# Flash.net
KiCad netlist of a schematic drawn in Altium Designer
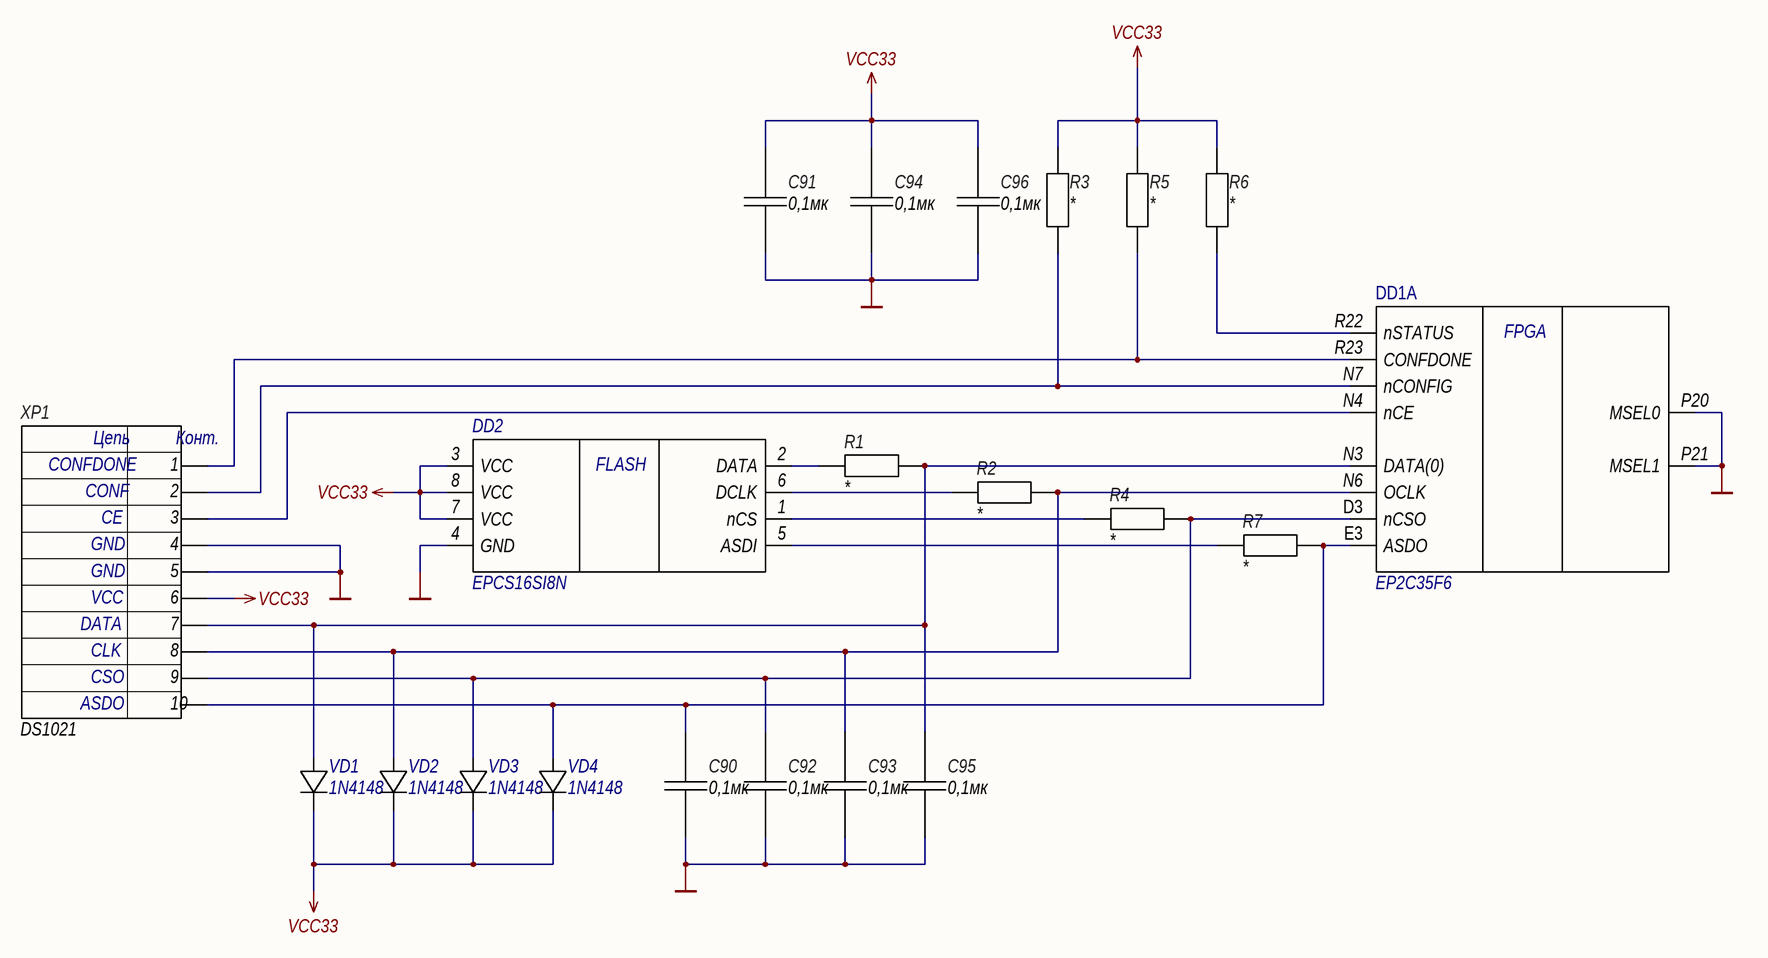
[diagram p0: Flash.SchDoc]

(export (version "E")
  (design (tool "Eeschema 10.0.6"))
  (components
    (comp (ref "C90")
      (value "0,1мк")
      (footprint "0603")
      (libsource (lib "FPGA_Automotibe_Radar_Lib") (part "Capacitor_0603"))
    )
    (comp (ref "C91")
      (value "0,1мк")
      (footprint "RESC1005X35N")
      (libsource (lib "FPGA_Automotibe_Radar_Lib") (part "Capacitor_0.1u"))
    )
    (comp (ref "C92")
      (value "0,1мк")
      (footprint "0603")
      (libsource (lib "FPGA_Automotibe_Radar_Lib") (part "Capacitor_0603"))
    )
    (comp (ref "C93")
      (value "0,1мк")
      (footprint "0603")
      (libsource (lib "FPGA_Automotibe_Radar_Lib") (part "Capacitor_0603"))
    )
    (comp (ref "C94")
      (value "0,1мк")
      (footprint "RESC1005X35N")
      (libsource (lib "FPGA_Automotibe_Radar_Lib") (part "Capacitor_0.1u"))
    )
    (comp (ref "C95")
      (value "0,1мк")
      (footprint "0603")
      (libsource (lib "FPGA_Automotibe_Radar_Lib") (part "Capacitor_0603"))
    )
    (comp (ref "C96")
      (value "0,1мк")
      (footprint "RESC1005X35N")
      (libsource (lib "FPGA_Automotibe_Radar_Lib") (part "Capacitor_0.1u"))
    )
    (comp (ref "DD1")
      (value "EP2C35F6")
      (footprint "BGA672CP100_26X26_2700X2700X240B60N")
      (libsource (lib "FPGA_Automotibe_Radar_Lib") (part "PLIS"))
    )
    (comp (ref "DD2")
      (value "EPCS16SI8N")
      (footprint "SOIC127P600X175-8N")
      (libsource (lib "FPGA_Automotibe_Radar_Lib") (part "FLASH"))
    )
    (comp (ref "R1")
      (value "*")
      (footprint "RESC3216X75N")
      (fields
        (field (name "TOLERANCE") "5%")
        (field (name "POWER") "0,1 Вт")
        (field (name "VALUEMANUFACTURERPARTNUMBER") "RC0603JR-07680RL")
      )
      (libsource (lib "FPGA_Automotibe_Radar_Lib") (part "Resistor"))
    )
    (comp (ref "R2")
      (value "*")
      (footprint "RESC3216X75N")
      (fields
        (field (name "TOLERANCE") "5%")
        (field (name "POWER") "0,1 Вт")
        (field (name "VALUEMANUFACTURERPARTNUMBER") "RC0603JR-07680RL")
      )
      (libsource (lib "FPGA_Automotibe_Radar_Lib") (part "Resistor"))
    )
    (comp (ref "R3")
      (value "*")
      (footprint "RESC3216X75N")
      (fields
        (field (name "TOLERANCE") "5%")
        (field (name "POWER") "0,1 Вт")
        (field (name "VALUEMANUFACTURERPARTNUMBER") "RC0603JR-07680RL")
      )
      (libsource (lib "FPGA_Automotibe_Radar_Lib") (part "Resistor_1206_10k"))
    )
    (comp (ref "R4")
      (value "*")
      (footprint "RESC3216X75N")
      (fields
        (field (name "TOLERANCE") "5%")
        (field (name "POWER") "0,1 Вт")
        (field (name "VALUEMANUFACTURERPARTNUMBER") "RC0603JR-07680RL")
      )
      (libsource (lib "FPGA_Automotibe_Radar_Lib") (part "Resistor"))
    )
    (comp (ref "R5")
      (value "*")
      (footprint "RESC3216X75N")
      (fields
        (field (name "TOLERANCE") "5%")
        (field (name "POWER") "0,1 Вт")
        (field (name "VALUEMANUFACTURERPARTNUMBER") "RC0603JR-07680RL")
      )
      (libsource (lib "FPGA_Automotibe_Radar_Lib") (part "Resistor_1206_10k"))
    )
    (comp (ref "R6")
      (value "*")
      (footprint "RESC3216X75N")
      (fields
        (field (name "TOLERANCE") "5%")
        (field (name "POWER") "0,1 Вт")
        (field (name "VALUEMANUFACTURERPARTNUMBER") "RC0603JR-07680RL")
      )
      (libsource (lib "FPGA_Automotibe_Radar_Lib") (part "Resistor_1206_10k"))
    )
    (comp (ref "R7")
      (value "*")
      (footprint "RESC3216X75N")
      (fields
        (field (name "TOLERANCE") "5%")
        (field (name "POWER") "0,1 Вт")
        (field (name "VALUEMANUFACTURERPARTNUMBER") "RC0603JR-07680RL")
      )
      (libsource (lib "FPGA_Automotibe_Radar_Lib") (part "Resistor"))
    )
    (comp (ref "VD1")
      (value "1N4148")
      (footprint "1N4148WVGS08")
      (libsource (lib "FPGA_Automotibe_Radar_Lib") (part "VD 1N41448"))
    )
    (comp (ref "VD2")
      (value "1N4148")
      (footprint "1N4148WVGS08")
      (libsource (lib "FPGA_Automotibe_Radar_Lib") (part "VD 1N41448"))
    )
    (comp (ref "VD3")
      (value "1N4148")
      (footprint "1N4148WVGS08")
      (libsource (lib "FPGA_Automotibe_Radar_Lib") (part "VD 1N41448"))
    )
    (comp (ref "VD4")
      (value "1N4148")
      (footprint "1N4148WVGS08")
      (libsource (lib "FPGA_Automotibe_Radar_Lib") (part "VD 1N41448"))
    )
    (comp (ref "XP1")
      (value "DS1021")
      (footprint "PBS-10")
      (libsource (lib "FPGA_Automotibe_Radar_Lib") (part "Header 10x1"))
    )
  )
  (nets
    (net (code "1") (name "GND") (class "Default")
      (node (ref "C90") (pin "2") (pinfunction "2_2") (pintype "passive"))
      (node (ref "C91") (pin "2") (pinfunction "2_2") (pintype "passive"))
      (node (ref "C92") (pin "2") (pinfunction "2_2") (pintype "passive"))
      (node (ref "C93") (pin "2") (pinfunction "2_2") (pintype "passive"))
      (node (ref "C94") (pin "2") (pinfunction "2_2") (pintype "passive"))
      (node (ref "C95") (pin "2") (pinfunction "2_2") (pintype "passive"))
      (node (ref "C96") (pin "2") (pinfunction "2_2") (pintype "passive"))
      (node (ref "DD1") (pin "P20") (pinfunction "MSEL0_P20") (pintype "passive"))
      (node (ref "DD1") (pin "P21") (pinfunction "MSEL1_P21") (pintype "passive"))
      (node (ref "DD2") (pin "4") (pinfunction "GND_4") (pintype "passive"))
      (node (ref "XP1") (pin "4") (pinfunction "4_4") (pintype "passive"))
      (node (ref "XP1") (pin "5") (pinfunction "5_5") (pintype "passive"))
    )
    (net (code "2") (name "Net-(DD1A-ASDO)") (class "Default")
      (node (ref "C90") (pin "1") (pinfunction "1_1") (pintype "passive"))
      (node (ref "DD1") (pin "E3") (pinfunction "ASDO_E3") (pintype "passive"))
      (node (ref "R7") (pin "2") (pinfunction "2_2") (pintype "passive"))
      (node (ref "VD4") (pin "2") (pinfunction "2_2") (pintype "passive"))
      (node (ref "XP1") (pin "10") (pinfunction "10_10") (pintype "passive"))
    )
    (net (code "3") (name "Net-(DD1A-CONFDONE)") (class "Default")
      (node (ref "DD1") (pin "R23") (pinfunction "CONFDONE_R23") (pintype "passive"))
      (node (ref "R5") (pin "1") (pinfunction "1_1") (pintype "passive"))
      (node (ref "XP1") (pin "1") (pinfunction "1_1") (pintype "passive"))
    )
    (net (code "4") (name "Net-(DD1A-DATA(0))") (class "Default")
      (node (ref "C95") (pin "1") (pinfunction "1_1") (pintype "passive"))
      (node (ref "DD1") (pin "N3") (pinfunction "DATA(0)_N3") (pintype "passive"))
      (node (ref "R1") (pin "2") (pinfunction "2_2") (pintype "passive"))
      (node (ref "VD1") (pin "2") (pinfunction "2_2") (pintype "passive"))
      (node (ref "XP1") (pin "7") (pinfunction "7_7") (pintype "passive"))
    )
    (net (code "5") (name "Net-(DD1A-OCLK)") (class "Default")
      (node (ref "C93") (pin "1") (pinfunction "1_1") (pintype "passive"))
      (node (ref "DD1") (pin "N6") (pinfunction "OCLK_N6") (pintype "passive"))
      (node (ref "R2") (pin "2") (pinfunction "2_2") (pintype "passive"))
      (node (ref "VD2") (pin "2") (pinfunction "2_2") (pintype "passive"))
      (node (ref "XP1") (pin "8") (pinfunction "8_8") (pintype "passive"))
    )
    (net (code "6") (name "Net-(DD1A-nCE)") (class "Default")
      (node (ref "DD1") (pin "N4") (pinfunction "nCE_N4") (pintype "passive"))
      (node (ref "XP1") (pin "3") (pinfunction "3_3") (pintype "passive"))
    )
    (net (code "7") (name "Net-(DD1A-nCONFIG)") (class "Default")
      (node (ref "DD1") (pin "N7") (pinfunction "nCONFIG_N7") (pintype "passive"))
      (node (ref "R3") (pin "1") (pinfunction "1_1") (pintype "passive"))
      (node (ref "XP1") (pin "2") (pinfunction "2_2") (pintype "passive"))
    )
    (net (code "8") (name "Net-(DD1A-nCSO)") (class "Default")
      (node (ref "C92") (pin "1") (pinfunction "1_1") (pintype "passive"))
      (node (ref "DD1") (pin "D3") (pinfunction "nCSO_D3") (pintype "passive"))
      (node (ref "R4") (pin "2") (pinfunction "2_2") (pintype "passive"))
      (node (ref "VD3") (pin "2") (pinfunction "2_2") (pintype "passive"))
      (node (ref "XP1") (pin "9") (pinfunction "9_9") (pintype "passive"))
    )
    (net (code "9") (name "Net-(DD1A-nSTATUS)") (class "Default")
      (node (ref "DD1") (pin "R22") (pinfunction "nSTATUS_R22") (pintype "passive"))
      (node (ref "R6") (pin "1") (pinfunction "1_1") (pintype "passive"))
    )
    (net (code "10") (name "Net-(DD2-ASDI)") (class "Default")
      (node (ref "DD2") (pin "5") (pinfunction "ASDI_5") (pintype "passive"))
      (node (ref "R7") (pin "1") (pinfunction "1_1") (pintype "passive"))
    )
    (net (code "11") (name "Net-(DD2-DATA)") (class "Default")
      (node (ref "DD2") (pin "2") (pinfunction "DATA_2") (pintype "passive"))
      (node (ref "R1") (pin "1") (pinfunction "1_1") (pintype "passive"))
    )
    (net (code "12") (name "Net-(DD2-DCLK)") (class "Default")
      (node (ref "DD2") (pin "6") (pinfunction "DCLK_6") (pintype "passive"))
      (node (ref "R2") (pin "1") (pinfunction "1_1") (pintype "passive"))
    )
    (net (code "13") (name "Net-(DD2-nCS)") (class "Default")
      (node (ref "DD2") (pin "1") (pinfunction "nCS_1") (pintype "passive"))
      (node (ref "R4") (pin "1") (pinfunction "1_1") (pintype "passive"))
    )
    (net (code "14") (name "VCC33") (class "Default")
      (node (ref "C91") (pin "1") (pinfunction "1_1") (pintype "passive"))
      (node (ref "C94") (pin "1") (pinfunction "1_1") (pintype "passive"))
      (node (ref "C96") (pin "1") (pinfunction "1_1") (pintype "passive"))
      (node (ref "DD2") (pin "3") (pinfunction "VCC_3") (pintype "passive"))
      (node (ref "DD2") (pin "7") (pinfunction "VCC_7") (pintype "passive"))
      (node (ref "DD2") (pin "8") (pinfunction "VCC_8") (pintype "passive"))
      (node (ref "R3") (pin "2") (pinfunction "2_2") (pintype "passive"))
      (node (ref "R5") (pin "2") (pinfunction "2_2") (pintype "passive"))
      (node (ref "R6") (pin "2") (pinfunction "2_2") (pintype "passive"))
      (node (ref "VD1") (pin "1") (pinfunction "1_1") (pintype "passive"))
      (node (ref "VD2") (pin "1") (pinfunction "1_1") (pintype "passive"))
      (node (ref "VD3") (pin "1") (pinfunction "1_1") (pintype "passive"))
      (node (ref "VD4") (pin "1") (pinfunction "1_1") (pintype "passive"))
      (node (ref "XP1") (pin "6") (pinfunction "6_6") (pintype "passive"))
    )
  )
)
